# Full_Bridge.net
KiCad netlist of a schematic drawn in Altium Designer
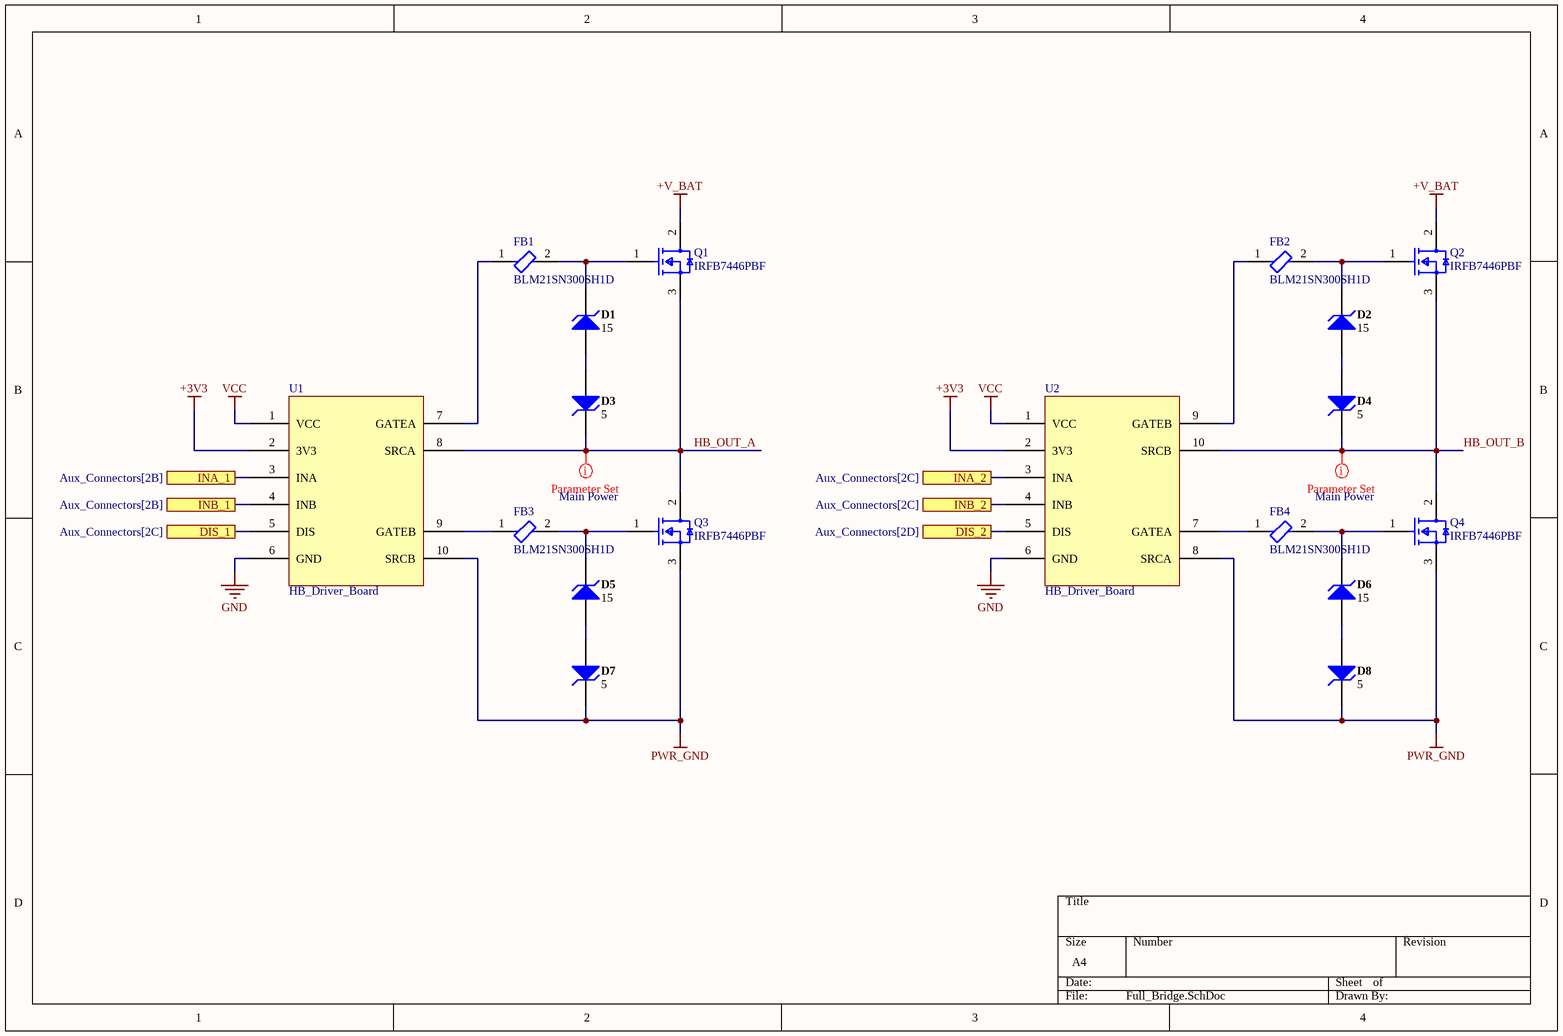
[diagram p0: Full_Bridge.SchDoc]

(export (version "E")
  (design (tool "Eeschema 10.0.6"))
  (components
    (comp (ref "D1")
      (value "15")
      (footprint "VISH-SOD-123-2_V")
      (description "Small Signal Zener Diode, 15 V +/- 5%, -55 to 155 degC, 2-Pin SOD-123, RoHS, Tape and Reel")
      (fields (field (name "MANUFACTURER") "Vishay Semiconductor") (field (name "TOLERANCE") "+/- 5%"))
      (libsource (lib "Altium Content Vault") (part "VISH-DZEN_A1K2-2"))
    )
    (comp (ref "D2")
      (value "15")
      (footprint "VISH-SOD-123-2_V")
      (description "Small Signal Zener Diode, 15 V +/- 5%, -55 to 155 degC, 2-Pin SOD-123, RoHS, Tape and Reel")
      (fields (field (name "MANUFACTURER") "Vishay Semiconductor") (field (name "TOLERANCE") "+/- 5%"))
      (libsource (lib "Altium Content Vault") (part "VISH-DZEN_A1K2-2"))
    )
    (comp (ref "D3")
      (value "5")
      (footprint "VISH-SOD-123-2_V")
      (description "Small Signal Zener Diode, 5.1 V +/- 5%, -55 to 155 degC, 2-Pin SOD-123, RoHS, Tape and Reel")
      (fields (field (name "TOLERANCE") "+/- 5%") (field (name "MANUFACTURER") "Vishay Semiconductor"))
      (libsource (lib "Altium Content Vault") (part "VISH-DZEN_A1K2-2"))
    )
    (comp (ref "D4")
      (value "5")
      (footprint "VISH-SOD-123-2_V")
      (description "Small Signal Zener Diode, 5.1 V +/- 5%, -55 to 155 degC, 2-Pin SOD-123, RoHS, Tape and Reel")
      (fields (field (name "TOLERANCE") "+/- 5%") (field (name "MANUFACTURER") "Vishay Semiconductor"))
      (libsource (lib "Altium Content Vault") (part "VISH-DZEN_A1K2-2"))
    )
    (comp (ref "D5")
      (value "15")
      (footprint "VISH-SOD-123-2_V")
      (description "Small Signal Zener Diode, 15 V +/- 5%, -55 to 155 degC, 2-Pin SOD-123, RoHS, Tape and Reel")
      (fields (field (name "MANUFACTURER") "Vishay Semiconductor") (field (name "TOLERANCE") "+/- 5%"))
      (libsource (lib "Altium Content Vault") (part "VISH-DZEN_A1K2-2"))
    )
    (comp (ref "D6")
      (value "15")
      (footprint "VISH-SOD-123-2_V")
      (description "Small Signal Zener Diode, 15 V +/- 5%, -55 to 155 degC, 2-Pin SOD-123, RoHS, Tape and Reel")
      (fields (field (name "MANUFACTURER") "Vishay Semiconductor") (field (name "TOLERANCE") "+/- 5%"))
      (libsource (lib "Altium Content Vault") (part "VISH-DZEN_A1K2-2"))
    )
    (comp (ref "D7")
      (value "5")
      (footprint "VISH-SOD-123-2_V")
      (description "Small Signal Zener Diode, 5.1 V +/- 5%, -55 to 155 degC, 2-Pin SOD-123, RoHS, Tape and Reel")
      (fields (field (name "TOLERANCE") "+/- 5%") (field (name "MANUFACTURER") "Vishay Semiconductor"))
      (libsource (lib "Altium Content Vault") (part "VISH-DZEN_A1K2-2"))
    )
    (comp (ref "D8")
      (value "5")
      (footprint "VISH-SOD-123-2_V")
      (description "Small Signal Zener Diode, 5.1 V +/- 5%, -55 to 155 degC, 2-Pin SOD-123, RoHS, Tape and Reel")
      (fields (field (name "TOLERANCE") "+/- 5%") (field (name "MANUFACTURER") "Vishay Semiconductor"))
      (libsource (lib "Altium Content Vault") (part "VISH-DZEN_A1K2-2"))
    )
    (comp (ref "FB1")
      (value "BLM21SN300SH1D")
      (footprint "FP-BLM21-0_2-t0_85-e0_5-d-IPC_A")
      (description "Chip Ferrite Bead, 0805, 30Ω @ 100MHz, 0.004Ω, ±10Ω, 8.5A")
      (libsource (lib "Altium Content Vault") (part "5f30dd21d616792df468990f7003faa"))
    )
    (comp (ref "FB2")
      (value "BLM21SN300SH1D")
      (footprint "FP-BLM21-0_2-t0_85-e0_5-d-IPC_A")
      (description "Chip Ferrite Bead, 0805, 30Ω @ 100MHz, 0.004Ω, ±10Ω, 8.5A")
      (libsource (lib "Altium Content Vault") (part "5f30dd21d616792df468990f7003faa"))
    )
    (comp (ref "FB3")
      (value "BLM21SN300SH1D")
      (footprint "FP-BLM21-0_2-t0_85-e0_5-d-IPC_A")
      (description "Chip Ferrite Bead, 0805, 30Ω @ 100MHz, 0.004Ω, ±10Ω, 8.5A")
      (libsource (lib "Altium Content Vault") (part "5f30dd21d616792df468990f7003faa"))
    )
    (comp (ref "FB4")
      (value "BLM21SN300SH1D")
      (footprint "FP-BLM21-0_2-t0_85-e0_5-d-IPC_A")
      (description "Chip Ferrite Bead, 0805, 30Ω @ 100MHz, 0.004Ω, ±10Ω, 8.5A")
      (libsource (lib "Altium Content Vault") (part "5f30dd21d616792df468990f7003faa"))
    )
    (comp (ref "Q1")
      (value "IRFB7446PBF")
      (footprint "FP-PG-TO220-3-MFG")
      (description "MOSFET N-CH 40V 120A TO220AB")
      (libsource (lib "Altium Content Vault") (part "b44c8776e10362b01251f5cff19d373"))
    )
    (comp (ref "Q2")
      (value "IRFB7446PBF")
      (footprint "FP-PG-TO220-3-MFG")
      (description "MOSFET N-CH 40V 120A TO220AB")
      (libsource (lib "Altium Content Vault") (part "b44c8776e10362b01251f5cff19d373"))
    )
    (comp (ref "Q3")
      (value "IRFB7446PBF")
      (footprint "FP-PG-TO220-3-MFG")
      (description "MOSFET N-CH 40V 120A TO220AB")
      (libsource (lib "Altium Content Vault") (part "b44c8776e10362b01251f5cff19d373"))
    )
    (comp (ref "Q4")
      (value "IRFB7446PBF")
      (footprint "FP-PG-TO220-3-MFG")
      (description "MOSFET N-CH 40V 120A TO220AB")
      (libsource (lib "Altium Content Vault") (part "b44c8776e10362b01251f5cff19d373"))
    )
    (comp (ref "U1")
      (value "HB_Driver_Board")
      (footprint "HB_Driver")
      (libsource (lib "") (part "HB_Driver_Board_1"))
    )
    (comp (ref "U2")
      (value "HB_Driver_Board")
      (footprint "HB_Driver")
      (libsource (lib "HB_Driver") (part "HB_Driver_Board"))
    )
  )
  (nets
    (net (code "1") (name "+3V3") (class "Default")
      (node (ref "U1") (pin "2") (pinfunction "3V3_2") (pintype "passive"))
      (node (ref "U2") (pin "2") (pinfunction "3V3_2") (pintype "passive"))
    )
    (net (code "2") (name "+V_BAT") (class "Default")
      (node (ref "Q1") (pin "2") (pinfunction "D_2") (pintype "passive"))
      (node (ref "Q2") (pin "2") (pinfunction "D_2") (pintype "passive"))
    )
    (net (code "3") (name "/DIS_1") (class "Default")
      (node (ref "U1") (pin "5") (pinfunction "DIS_5") (pintype "passive"))
    )
    (net (code "4") (name "/DIS_2") (class "Default")
      (node (ref "U2") (pin "5") (pinfunction "DIS_5") (pintype "passive"))
    )
    (net (code "5") (name "/HB_OUT_A") (class "Default")
      (node (ref "D3") (pin "2") (pinfunction "K_2") (pintype "passive"))
      (node (ref "Q1") (pin "3") (pinfunction "S_3") (pintype "passive"))
      (node (ref "Q3") (pin "2") (pinfunction "D_2") (pintype "passive"))
      (node (ref "U1") (pin "8") (pinfunction "SRCA_8") (pintype "passive"))
    )
    (net (code "6") (name "/HB_OUT_B") (class "Default")
      (node (ref "D4") (pin "2") (pinfunction "K_2") (pintype "passive"))
      (node (ref "Q2") (pin "3") (pinfunction "S_3") (pintype "passive"))
      (node (ref "Q4") (pin "2") (pinfunction "D_2") (pintype "passive"))
      (node (ref "U2") (pin "10") (pinfunction "SRCB_10") (pintype "passive"))
    )
    (net (code "7") (name "/INA_1") (class "Default")
      (node (ref "U1") (pin "3") (pinfunction "INA_3") (pintype "passive"))
    )
    (net (code "8") (name "/INA_2") (class "Default")
      (node (ref "U2") (pin "3") (pinfunction "INA_3") (pintype "passive"))
    )
    (net (code "9") (name "/INB_1") (class "Default")
      (node (ref "U1") (pin "4") (pinfunction "INB_4") (pintype "passive"))
    )
    (net (code "10") (name "/INB_2") (class "Default")
      (node (ref "U2") (pin "4") (pinfunction "INB_4") (pintype "passive"))
    )
    (net (code "11") (name "GND") (class "Default")
      (node (ref "U1") (pin "6") (pinfunction "GND_6") (pintype "passive"))
      (node (ref "U2") (pin "6") (pinfunction "GND_6") (pintype "passive"))
    )
    (net (code "12") (name "Net-(D1-A)") (class "Default")
      (node (ref "D1") (pin "1") (pinfunction "A_1") (pintype "passive"))
      (node (ref "D3") (pin "1") (pinfunction "A_1") (pintype "passive"))
    )
    (net (code "13") (name "Net-(D1-K)") (class "Default")
      (node (ref "D1") (pin "2") (pinfunction "K_2") (pintype "passive"))
      (node (ref "FB1") (pin "2") (pinfunction "2_2") (pintype "passive"))
      (node (ref "Q1") (pin "1") (pinfunction "G_1") (pintype "passive"))
    )
    (net (code "14") (name "Net-(D2-A)") (class "Default")
      (node (ref "D2") (pin "1") (pinfunction "A_1") (pintype "passive"))
      (node (ref "D4") (pin "1") (pinfunction "A_1") (pintype "passive"))
    )
    (net (code "15") (name "Net-(D2-K)") (class "Default")
      (node (ref "D2") (pin "2") (pinfunction "K_2") (pintype "passive"))
      (node (ref "FB2") (pin "2") (pinfunction "2_2") (pintype "passive"))
      (node (ref "Q2") (pin "1") (pinfunction "G_1") (pintype "passive"))
    )
    (net (code "16") (name "Net-(D5-A)") (class "Default")
      (node (ref "D5") (pin "1") (pinfunction "A_1") (pintype "passive"))
      (node (ref "D7") (pin "1") (pinfunction "A_1") (pintype "passive"))
    )
    (net (code "17") (name "Net-(D5-K)") (class "Default")
      (node (ref "D5") (pin "2") (pinfunction "K_2") (pintype "passive"))
      (node (ref "FB3") (pin "2") (pinfunction "2_2") (pintype "passive"))
      (node (ref "Q3") (pin "1") (pinfunction "G_1") (pintype "passive"))
    )
    (net (code "18") (name "Net-(D6-A)") (class "Default")
      (node (ref "D6") (pin "1") (pinfunction "A_1") (pintype "passive"))
      (node (ref "D8") (pin "1") (pinfunction "A_1") (pintype "passive"))
    )
    (net (code "19") (name "Net-(D6-K)") (class "Default")
      (node (ref "D6") (pin "2") (pinfunction "K_2") (pintype "passive"))
      (node (ref "FB4") (pin "2") (pinfunction "2_2") (pintype "passive"))
      (node (ref "Q4") (pin "1") (pinfunction "G_1") (pintype "passive"))
    )
    (net (code "20") (name "Net-(U1-GATEA)") (class "Default")
      (node (ref "FB1") (pin "1") (pinfunction "1_1") (pintype "passive"))
      (node (ref "U1") (pin "7") (pinfunction "GATEA_7") (pintype "passive"))
    )
    (net (code "21") (name "Net-(U1-GATEB)") (class "Default")
      (node (ref "FB3") (pin "1") (pinfunction "1_1") (pintype "passive"))
      (node (ref "U1") (pin "9") (pinfunction "GATEB_9") (pintype "passive"))
    )
    (net (code "22") (name "Net-(U2-GATEA)") (class "Default")
      (node (ref "FB4") (pin "1") (pinfunction "1_1") (pintype "passive"))
      (node (ref "U2") (pin "7") (pinfunction "GATEA_7") (pintype "passive"))
    )
    (net (code "23") (name "Net-(U2-GATEB)") (class "Default")
      (node (ref "FB2") (pin "1") (pinfunction "1_1") (pintype "passive"))
      (node (ref "U2") (pin "9") (pinfunction "GATEB_9") (pintype "passive"))
    )
    (net (code "24") (name "PWR_GND") (class "Default")
      (node (ref "D7") (pin "2") (pinfunction "K_2") (pintype "passive"))
      (node (ref "D8") (pin "2") (pinfunction "K_2") (pintype "passive"))
      (node (ref "Q3") (pin "3") (pinfunction "S_3") (pintype "passive"))
      (node (ref "Q4") (pin "3") (pinfunction "S_3") (pintype "passive"))
      (node (ref "U1") (pin "10") (pinfunction "SRCB_10") (pintype "passive"))
      (node (ref "U2") (pin "8") (pinfunction "SRCA_8") (pintype "passive"))
    )
    (net (code "25") (name "VCC") (class "Default")
      (node (ref "U1") (pin "1") (pinfunction "VCC_1") (pintype "passive"))
      (node (ref "U2") (pin "1") (pinfunction "VCC_1") (pintype "passive"))
    )
  )
)
